# l293d.net
KiCad netlist of a schematic drawn in EAGLE
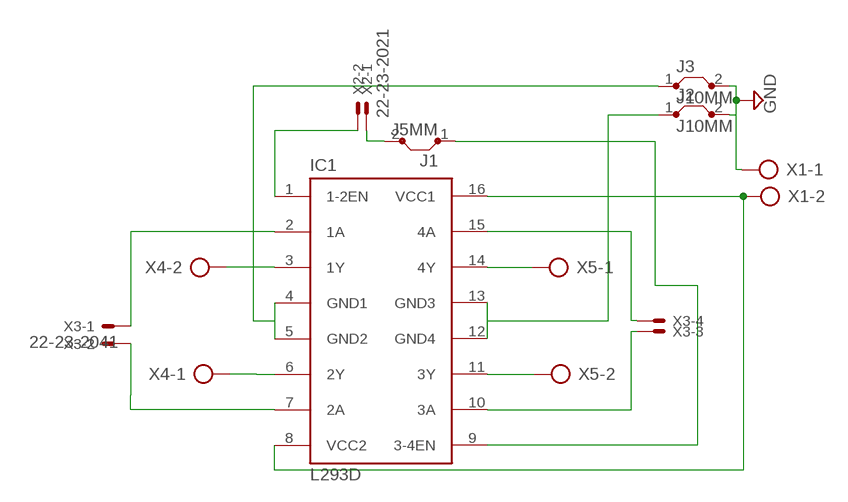
[diagram p0: schematic, sheet 1]

(export (version "E")
  (design (tool "Eeschema 10.0.6"))
  (components
    (comp (ref "IC1")
      (value "L293D")
      (footprint "eagle-import:DIL16")
      (libsource (lib "eagle-import") (part "L293D"))
    )
    (comp (ref "J1")
      (value "J5MM")
      (footprint "eagle-import:05")
      (libsource (lib "eagle-import") (part "J5MM"))
    )
    (comp (ref "J2")
      (value "J10MM")
      (footprint "eagle-import:10")
      (libsource (lib "eagle-import") (part "J10MM"))
    )
    (comp (ref "J3")
      (value "J10MM")
      (footprint "eagle-import:10")
      (libsource (lib "eagle-import") (part "J10MM"))
    )
    (comp (ref "X1")
      (value "AK500/2")
      (footprint "eagle-import:AK500_2")
      (libsource (lib "eagle-import") (part "AK500/2"))
    )
    (comp (ref "X2")
      (value "22-23-2021")
      (footprint "eagle-import:22-23-2021")
      (fields (field (name "MF") "MOLEX"))
      (libsource (lib "eagle-import") (part "22-23-2021"))
    )
    (comp (ref "X3")
      (value "22-23-2041")
      (footprint "eagle-import:22-23-2041")
      (fields (field (name "MF") "MOLEX"))
      (libsource (lib "eagle-import") (part "22-23-2041"))
    )
    (comp (ref "X4")
      (value "AK500/2")
      (footprint "eagle-import:AK500_2")
      (libsource (lib "eagle-import") (part "AK500/2"))
    )
    (comp (ref "X5")
      (value "AK500/2")
      (footprint "eagle-import:AK500_2")
      (libsource (lib "eagle-import") (part "AK500/2"))
    )
  )
  (nets
    (net (code "1") (name "GND") (class "Default")
      (node (ref "J2") (pin "2") (pinfunction "2_2") (pintype "passive"))
      (node (ref "J3") (pin "2") (pinfunction "2_2") (pintype "passive"))
      (node (ref "X1") (pin "1") (pinfunction "KL_1") (pintype "passive"))
    )
    (net (code "2") (name "Net-(IC1-1-2EN)") (class "Default")
      (node (ref "IC1") (pin "1") (pinfunction "1-2EN_1") (pintype "input"))
      (node (ref "X2") (pin "2") (pinfunction "S_2") (pintype "passive"))
    )
    (net (code "3") (name "Net-(IC1-1A)") (class "Default")
      (node (ref "IC1") (pin "2") (pinfunction "1A_2") (pintype "input"))
      (node (ref "X3") (pin "1") (pinfunction "S_1") (pintype "passive"))
    )
    (net (code "4") (name "Net-(IC1-1Y)") (class "Default")
      (node (ref "IC1") (pin "3") (pinfunction "1Y_3") (pintype "output"))
      (node (ref "X4") (pin "2") (pinfunction "KL_2") (pintype "passive"))
    )
    (net (code "5") (name "Net-(IC1-2A)") (class "Default")
      (node (ref "IC1") (pin "7") (pinfunction "2A_7") (pintype "input"))
      (node (ref "X3") (pin "2") (pinfunction "S_2") (pintype "passive"))
    )
    (net (code "6") (name "Net-(IC1-2Y)") (class "Default")
      (node (ref "IC1") (pin "6") (pinfunction "2Y_6") (pintype "output"))
      (node (ref "X4") (pin "1") (pinfunction "KL_1") (pintype "passive"))
    )
    (net (code "7") (name "Net-(IC1-3-4EN)") (class "Default")
      (node (ref "IC1") (pin "9") (pinfunction "3-4EN_9") (pintype "input"))
      (node (ref "J1") (pin "1") (pinfunction "1_1") (pintype "passive"))
    )
    (net (code "8") (name "Net-(IC1-3A)") (class "Default")
      (node (ref "IC1") (pin "10") (pinfunction "3A_10") (pintype "input"))
      (node (ref "X3") (pin "3") (pinfunction "S_3") (pintype "passive"))
    )
    (net (code "9") (name "Net-(IC1-3Y)") (class "Default")
      (node (ref "IC1") (pin "11") (pinfunction "3Y_11") (pintype "output"))
      (node (ref "X5") (pin "2") (pinfunction "KL_2") (pintype "passive"))
    )
    (net (code "10") (name "Net-(IC1-4A)") (class "Default")
      (node (ref "IC1") (pin "15") (pinfunction "4A_15") (pintype "input"))
      (node (ref "X3") (pin "4") (pinfunction "S_4") (pintype "passive"))
    )
    (net (code "11") (name "Net-(IC1-4Y)") (class "Default")
      (node (ref "IC1") (pin "14") (pinfunction "4Y_14") (pintype "output"))
      (node (ref "X5") (pin "1") (pinfunction "KL_1") (pintype "passive"))
    )
    (net (code "12") (name "Net-(IC1-GND1)") (class "Default")
      (node (ref "IC1") (pin "4") (pinfunction "GND1_4") (pintype "power_in"))
      (node (ref "IC1") (pin "5") (pinfunction "GND2_5") (pintype "power_in"))
      (node (ref "J3") (pin "1") (pinfunction "1_1") (pintype "passive"))
    )
    (net (code "13") (name "Net-(IC1-GND3)") (class "Default")
      (node (ref "IC1") (pin "12") (pinfunction "GND4_12") (pintype "power_in"))
      (node (ref "IC1") (pin "13") (pinfunction "GND3_13") (pintype "power_in"))
      (node (ref "J2") (pin "1") (pinfunction "1_1") (pintype "passive"))
    )
    (net (code "14") (name "Net-(IC1-VCC1)") (class "Default")
      (node (ref "IC1") (pin "16") (pinfunction "VCC1_16") (pintype "power_in"))
      (node (ref "IC1") (pin "8") (pinfunction "VCC2_8") (pintype "power_in"))
      (node (ref "X1") (pin "2") (pinfunction "KL_2") (pintype "passive"))
    )
    (net (code "15") (name "Net-(X2A-S)") (class "Default")
      (node (ref "J1") (pin "2") (pinfunction "2_2") (pintype "passive"))
      (node (ref "X2") (pin "1") (pinfunction "S_1") (pintype "passive"))
    )
  )
)
